# USB_3.net
KiCad netlist of a schematic drawn in Altium Designer
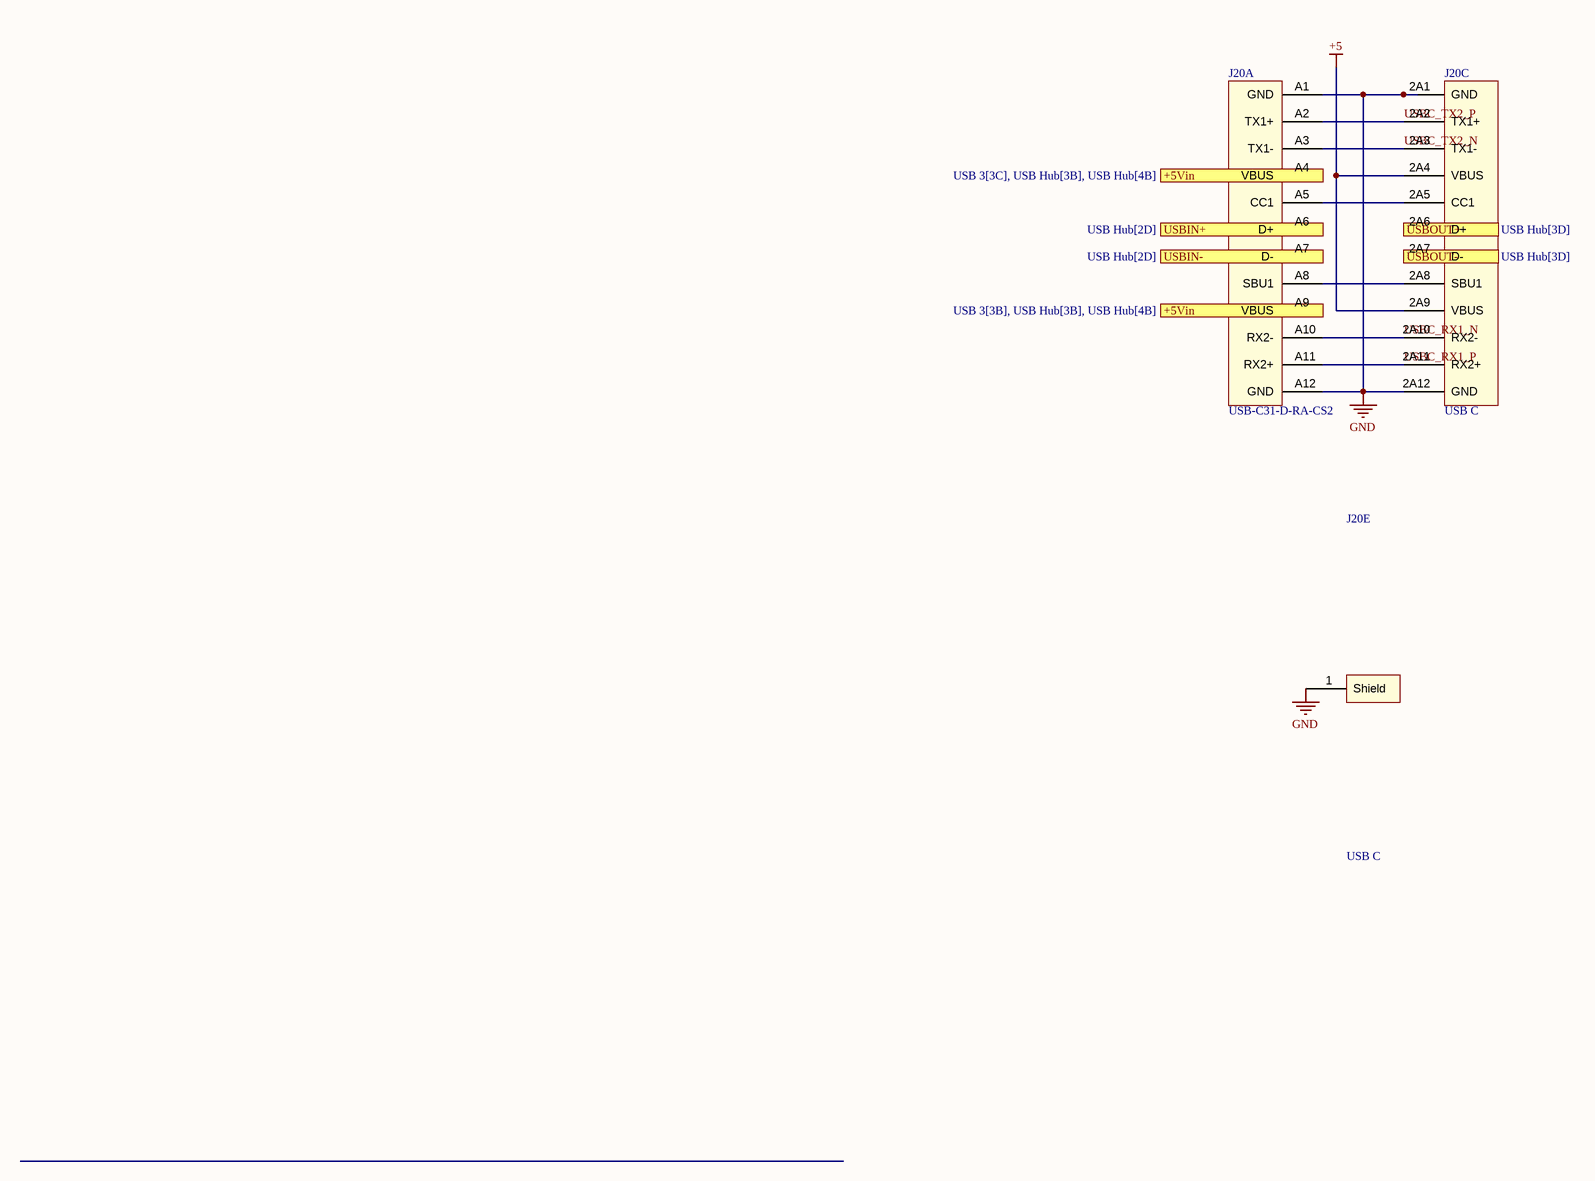
[diagram p0: USB 3.SchDoc]

(export (version "E")
  (design (tool "Eeschema 10.0.6"))
  (components
    (comp (ref "J20")
      (value "USB-C31-D-RA-CS2")
      (footprint "Dual USB C Connector")
      (description "Dual USB C Connector")
      (libsource (lib "Schlib1") (part "USB C"))
    )
  )
  (nets
    (net (code "1") (name "+5") (class "Default")
      (node (ref "J20") (pin "2A4") (pinfunction "VBUS_2A4") (pintype "passive"))
      (node (ref "J20") (pin "2A9") (pinfunction "VBUS_2A9") (pintype "passive"))
    )
    (net (code "2") (name "/+5Vin") (class "Default")
      (node (ref "J20") (pin "A4") (pinfunction "VBUS_A4") (pintype "passive"))
      (node (ref "J20") (pin "A9") (pinfunction "VBUS_A9") (pintype "passive"))
    )
    (net (code "3") (name "/USBC_RX1_N") (class "Default")
      (node (ref "J20") (pin "2A10") (pinfunction "RX2-_2A10") (pintype "passive"))
      (node (ref "J20") (pin "A10") (pinfunction "RX2-_A10") (pintype "passive"))
    )
    (net (code "4") (name "/USBC_RX1_P") (class "Default")
      (node (ref "J20") (pin "2A11") (pinfunction "RX2+_2A11") (pintype "passive"))
      (node (ref "J20") (pin "A11") (pinfunction "RX2+_A11") (pintype "passive"))
    )
    (net (code "5") (name "/USBC_TX2_N") (class "Default")
      (node (ref "J20") (pin "2A3") (pinfunction "TX1-_2A3") (pintype "passive"))
      (node (ref "J20") (pin "A3") (pinfunction "TX1-_A3") (pintype "passive"))
    )
    (net (code "6") (name "/USBC_TX2_P") (class "Default")
      (node (ref "J20") (pin "2A2") (pinfunction "TX1+_2A2") (pintype "passive"))
      (node (ref "J20") (pin "A2") (pinfunction "TX1+_A2") (pintype "passive"))
    )
    (net (code "7") (name "/USBIN+") (class "Default")
      (node (ref "J20") (pin "A6") (pinfunction "D+_A6") (pintype "passive"))
    )
    (net (code "8") (name "/USBIN-") (class "Default")
      (node (ref "J20") (pin "A7") (pinfunction "D-_A7") (pintype "passive"))
    )
    (net (code "9") (name "/USBOUT+") (class "Default")
      (node (ref "J20") (pin "2A6") (pinfunction "D+_2A6") (pintype "passive"))
    )
    (net (code "10") (name "/USBOUT-") (class "Default")
      (node (ref "J20") (pin "2A7") (pinfunction "D-_2A7") (pintype "passive"))
    )
    (net (code "11") (name "GND") (class "Default")
      (node (ref "J20") (pin "1") (pinfunction "Shield_1") (pintype "passive"))
      (node (ref "J20") (pin "2A1") (pinfunction "GND_2A1") (pintype "passive"))
      (node (ref "J20") (pin "2A12") (pinfunction "GND_2A12") (pintype "passive"))
      (node (ref "J20") (pin "A1") (pinfunction "GND_A1") (pintype "passive"))
      (node (ref "J20") (pin "A12") (pinfunction "GND_A12") (pintype "passive"))
    )
    (net (code "12") (name "Net-(J20A-CC1)") (class "Default")
      (node (ref "J20") (pin "2A5") (pinfunction "CC1_2A5") (pintype "passive"))
      (node (ref "J20") (pin "A5") (pinfunction "CC1_A5") (pintype "passive"))
    )
    (net (code "13") (name "Net-(J20A-SBU1)") (class "Default")
      (node (ref "J20") (pin "2A8") (pinfunction "SBU1_2A8") (pintype "passive"))
      (node (ref "J20") (pin "A8") (pinfunction "SBU1_A8") (pintype "passive"))
    )
  )
)
